# optocoupler_alarm.net
KiCad netlist of a schematic drawn in EAGLE
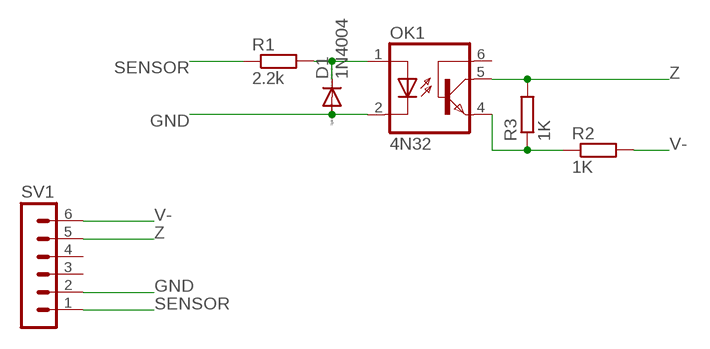
[diagram p0: schematic, sheet 1]

(export (version "E")
  (design (tool "Eeschema 10.0.6"))
  (components
    (comp (ref "D1")
      (value "1N4004")
      (footprint "eagle-import:DO41-10")
      (libsource (lib "eagle-import") (part "1N4004"))
    )
    (comp (ref "OK1")
      (value "4N32")
      (footprint "eagle-import:DIL06")
      (fields (field (name "MPN") "4N35-M"))
      (libsource (lib "eagle-import") (part "4N?M35"))
    )
    (comp (ref "R1")
      (value "2.2k")
      (footprint "eagle-import:0207_10")
      (libsource (lib "eagle-import") (part "R-EU_0207/10"))
    )
    (comp (ref "R2")
      (value "1K")
      (footprint "eagle-import:0207_10")
      (libsource (lib "eagle-import") (part "R-EU_0207/10"))
    )
    (comp (ref "R3")
      (value "1K")
      (footprint "eagle-import:0207_10")
      (libsource (lib "eagle-import") (part "R-EU_0207/10"))
    )
    (comp (ref "SV1")
      (value "MA06-1")
      (footprint "eagle-import:MA06-1")
      (libsource (lib "eagle-import") (part "MA06-1"))
    )
  )
  (nets
    (net (code "1") (name "/GND") (class "Default")
      (node (ref "D1") (pin "A") (pinfunction "A_A") (pintype "passive"))
      (node (ref "OK1") (pin "2") (pinfunction "C_2") (pintype "passive"))
      (node (ref "SV1") (pin "2") (pinfunction "2_2") (pintype "passive"))
    )
    (net (code "2") (name "/SENSOR") (class "Default")
      (node (ref "R1") (pin "1") (pinfunction "1_1") (pintype "passive"))
      (node (ref "SV1") (pin "1") (pinfunction "1_1") (pintype "passive"))
    )
    (net (code "3") (name "/V-") (class "Default")
      (node (ref "R2") (pin "2") (pinfunction "2_2") (pintype "passive"))
      (node (ref "SV1") (pin "6") (pinfunction "6_6") (pintype "passive"))
    )
    (net (code "4") (name "/Z") (class "Default")
      (node (ref "OK1") (pin "5") (pinfunction "COL_5") (pintype "passive"))
      (node (ref "R3") (pin "2") (pinfunction "2_2") (pintype "passive"))
      (node (ref "SV1") (pin "5") (pinfunction "5_5") (pintype "passive"))
    )
    (net (code "5") (name "Net-(OK1-A)") (class "Default")
      (node (ref "D1") (pin "C") (pinfunction "C_C") (pintype "passive"))
      (node (ref "OK1") (pin "1") (pinfunction "A_1") (pintype "passive"))
      (node (ref "R1") (pin "2") (pinfunction "2_2") (pintype "passive"))
    )
    (net (code "6") (name "Net-(OK1-EMI)") (class "Default")
      (node (ref "OK1") (pin "4") (pinfunction "EMI_4") (pintype "passive"))
      (node (ref "R2") (pin "1") (pinfunction "1_1") (pintype "passive"))
      (node (ref "R3") (pin "1") (pinfunction "1_1") (pintype "passive"))
    )
    (net (code "7") (name "unconnected-(OK1-BAS-Pad6)") (class "Default")
      (node (ref "OK1") (pin "6") (pinfunction "BAS_6") (pintype "passive"))
    )
    (net (code "8") (name "unconnected-(SV1-Pad3)") (class "Default")
      (node (ref "SV1") (pin "3") (pinfunction "3_3") (pintype "passive"))
    )
    (net (code "9") (name "unconnected-(SV1-Pad4)") (class "Default")
      (node (ref "SV1") (pin "4") (pinfunction "4_4") (pintype "passive"))
    )
  )
)
